# led_RGB_schematic.net
KiCad netlist of a schematic drawn in Altium Designer
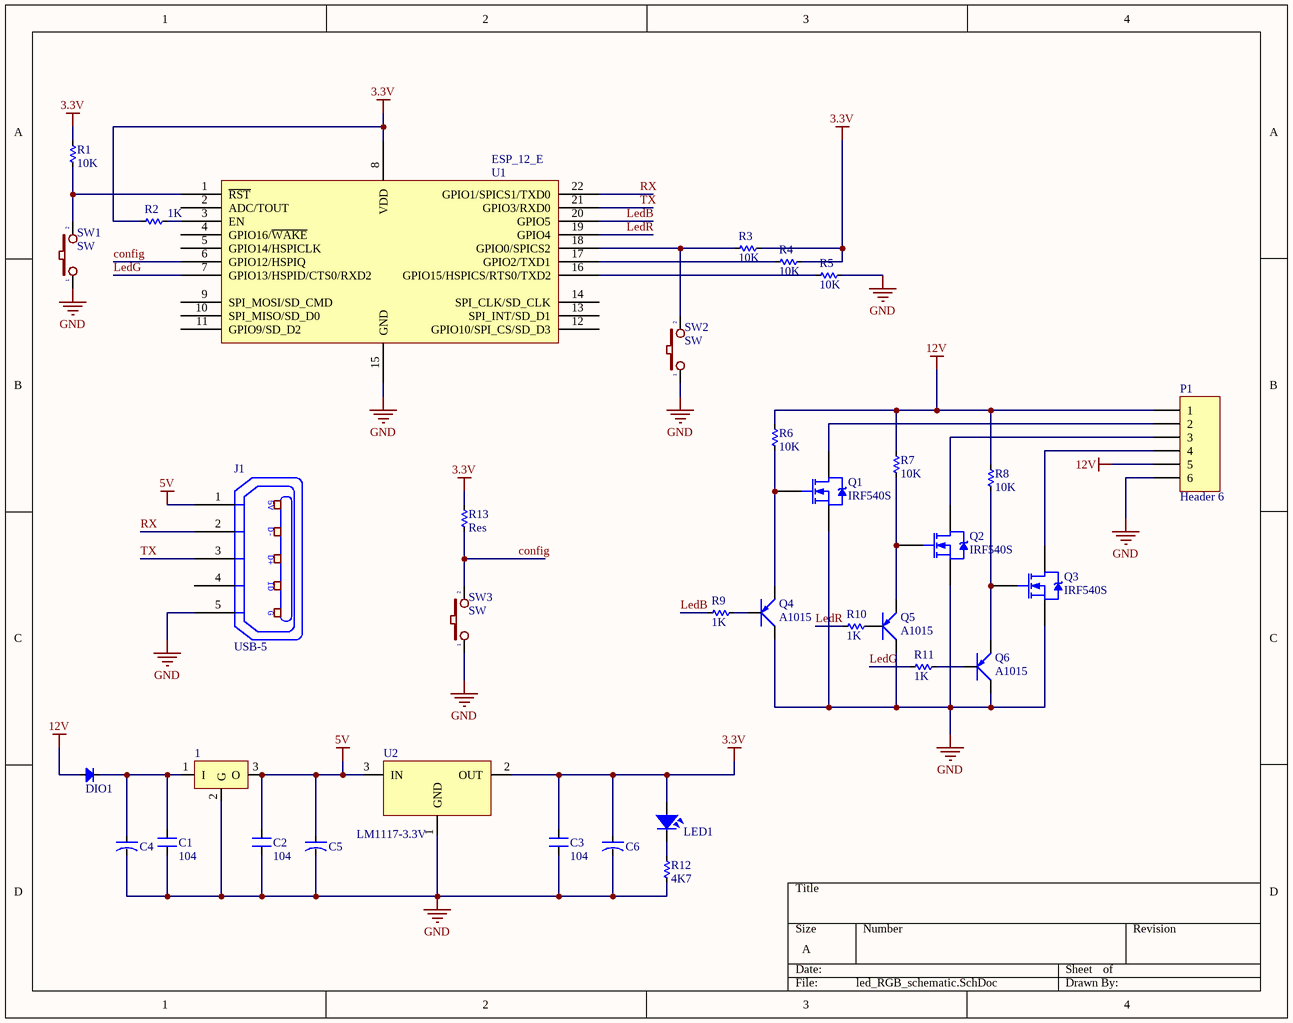
[diagram p0: led_RGB_schematic.SchDoc]

(export (version "E")
  (design (tool "Eeschema 10.0.6"))
  (components
    (comp (ref "1")
      (value "LM78xx")
      (footprint "TO252-123")
      (description "Positive Voltage Regulator")
      (fields (field (name "PUBLISHER") "Altium Limited"))
      (libsource (lib "LIBRARY") (part "LM78xx"))
    )
    (comp (ref "C1")
      (value "104")
      (footprint "SM-CAP-0805")
      (fields (field (name "DESIGNED BY") "VanDungEvn"))
      (libsource (lib "electronicvn-library1") (part "CN"))
    )
    (comp (ref "C2")
      (value "104")
      (footprint "SM-CAP-0805")
      (fields (field (name "DESIGNED BY") "VanDungEvn"))
      (libsource (lib "electronicvn-library1") (part "CN"))
    )
    (comp (ref "C3")
      (value "104")
      (footprint "SM-CAP-0805")
      (fields (field (name "DESIGNED BY") "VanDungEvn"))
      (libsource (lib "electronicvn-library1") (part "CN"))
    )
    (comp (ref "C4")
      (value "CN-ALU-SMD")
      (footprint "CAP-ALU-SMD-4.5x5x1.4")
      (description "Polarized Capacitor (Axial)")
      (fields (field (name "PUBLISHER") "Altium Limited"))
      (libsource (lib "LIBTanCN") (part "CN-ALU-SMD"))
    )
    (comp (ref "C5")
      (value "CN-ALU-SMD")
      (footprint "CAP-ALU-SMD-4.5x5x1.4")
      (description "Polarized Capacitor (Axial)")
      (fields (field (name "PUBLISHER") "Altium Limited"))
      (libsource (lib "LIBTanCN") (part "CN-ALU-SMD"))
    )
    (comp (ref "C6")
      (value "CN-ALU-SMD")
      (footprint "CAP-ALU-SMD-4.5x5x1.4")
      (description "Polarized Capacitor (Axial)")
      (fields (field (name "PUBLISHER") "Altium Limited"))
      (libsource (lib "LIBTanCN") (part "CN-ALU-SMD"))
    )
    (comp (ref "DIO1")
      (value "Diode SMD")
      (footprint "DIO-SMD-106")
      (description "Default Diode")
      (fields (field (name "PUBLISHER") "Altium Limited"))
      (libsource (lib "LIBRARY") (part "Diode SMD"))
    )
    (comp (ref "J1")
      (value "USB-5")
      (footprint "USB-M1")
      (fields
        (field (name "MANUFACTURER") "FCI")
        (field (name "MANUFACTURER PART NUMBER") "10118193-0001LF")
        (field (name ".CREATOR") "MM")
        (field (name ".CHECKED PCB") "RF")
        (field (name ".CHECKED SCH") "MM")
      )
      (libsource (lib "LIBRARY") (part "USB-5"))
    )
    (comp (ref "LED1") (value "LED") (footprint "LED-0805-Blue") (libsource (lib "LIBRARY") (part "LED SMD")))
    (comp (ref "P1")
      (value "Header 6")
      (footprint "HED6T")
      (description "Header, 6-Pin")
      (fields (field (name "PUBLISHER") "Altium Limited"))
      (libsource (lib "LIBTanCN") (part "Header 6"))
    )
    (comp (ref "Q1")
      (value "IRF540S")
      (footprint "D2PAK_N")
      (description "HEXFET N-Channel Power MOSFET")
      (fields (field (name "PUBLISHER") "Altium Limited"))
      (libsource (lib "IR Discrete MOSFET - Power") (part "IRF540S"))
    )
    (comp (ref "Q2")
      (value "IRF540S")
      (footprint "D2PAK_N")
      (description "HEXFET N-Channel Power MOSFET")
      (fields (field (name "PUBLISHER") "Altium Limited"))
      (libsource (lib "IR Discrete MOSFET - Power") (part "IRF540S"))
    )
    (comp (ref "Q3")
      (value "IRF540S")
      (footprint "D2PAK_N")
      (description "HEXFET N-Channel Power MOSFET")
      (fields (field (name "PUBLISHER") "Altium Limited"))
      (libsource (lib "IR Discrete MOSFET - Power") (part "IRF540S"))
    )
    (comp (ref "Q4")
      (value "A1015")
      (footprint "SOT23B")
      (description "PNP 600mW, ECB")
      (libsource (lib "electronicvn-library1") (part "A1015"))
    )
    (comp (ref "Q5")
      (value "A1015")
      (footprint "SOT23B")
      (description "PNP 600mW, ECB")
      (libsource (lib "electronicvn-library1") (part "A1015"))
    )
    (comp (ref "Q6")
      (value "A1015")
      (footprint "SOT23B")
      (description "PNP 600mW, ECB")
      (libsource (lib "electronicvn-library1") (part "A1015"))
    )
    (comp (ref "R1")
      (value "10K")
      (footprint "RES-SMD-0805")
      (description "Resistor")
      (fields
        (field (name "MANUFACTURER") "Generic Components")
        (field (name "PUBLISHER") "Altium Hobart Technology Centre")
      )
      (libsource (lib "LIBRARY") (part "Res-SMD"))
    )
    (comp (ref "R2")
      (value "1K")
      (footprint "RES-SMD-0805")
      (description "Resistor")
      (fields
        (field (name "MANUFACTURER") "Generic Components")
        (field (name "PUBLISHER") "Altium Hobart Technology Centre")
      )
      (libsource (lib "LIBRARY") (part "Res-SMD"))
    )
    (comp (ref "R3")
      (value "10K")
      (footprint "RES-SMD-0805")
      (description "Resistor")
      (fields
        (field (name "MANUFACTURER") "Generic Components")
        (field (name "PUBLISHER") "Altium Hobart Technology Centre")
      )
      (libsource (lib "LIBRARY") (part "Res-SMD"))
    )
    (comp (ref "R4")
      (value "10K")
      (footprint "RES-SMD-0805")
      (description "Resistor")
      (fields
        (field (name "MANUFACTURER") "Generic Components")
        (field (name "PUBLISHER") "Altium Hobart Technology Centre")
      )
      (libsource (lib "LIBRARY") (part "Res-SMD"))
    )
    (comp (ref "R5")
      (value "10K")
      (footprint "RES-SMD-0805")
      (description "Resistor")
      (fields
        (field (name "MANUFACTURER") "Generic Components")
        (field (name "PUBLISHER") "Altium Hobart Technology Centre")
      )
      (libsource (lib "LIBRARY") (part "Res-SMD"))
    )
    (comp (ref "R6")
      (value "10K")
      (footprint "RES-SMD-0805")
      (description "Resistor")
      (fields
        (field (name "MANUFACTURER") "Generic Components")
        (field (name "PUBLISHER") "Altium Hobart Technology Centre")
      )
      (libsource (lib "LIBRARY") (part "Res-SMD"))
    )
    (comp (ref "R7")
      (value "10K")
      (footprint "RES-SMD-0805")
      (description "Resistor")
      (fields
        (field (name "MANUFACTURER") "Generic Components")
        (field (name "PUBLISHER") "Altium Hobart Technology Centre")
      )
      (libsource (lib "LIBRARY") (part "Res-SMD"))
    )
    (comp (ref "R8")
      (value "10K")
      (footprint "RES-SMD-0805")
      (description "Resistor")
      (fields
        (field (name "MANUFACTURER") "Generic Components")
        (field (name "PUBLISHER") "Altium Hobart Technology Centre")
      )
      (libsource (lib "LIBRARY") (part "Res-SMD"))
    )
    (comp (ref "R9")
      (value "1K")
      (footprint "RES-SMD-0805")
      (description "Resistor")
      (fields
        (field (name "MANUFACTURER") "Generic Components")
        (field (name "PUBLISHER") "Altium Hobart Technology Centre")
      )
      (libsource (lib "LIBRARY") (part "Res-SMD"))
    )
    (comp (ref "R10")
      (value "1K")
      (footprint "RES-SMD-0805")
      (description "Resistor")
      (fields
        (field (name "MANUFACTURER") "Generic Components")
        (field (name "PUBLISHER") "Altium Hobart Technology Centre")
      )
      (libsource (lib "LIBRARY") (part "Res-SMD"))
    )
    (comp (ref "R11")
      (value "1K")
      (footprint "RES-SMD-0805")
      (description "Resistor")
      (fields
        (field (name "MANUFACTURER") "Generic Components")
        (field (name "PUBLISHER") "Altium Hobart Technology Centre")
      )
      (libsource (lib "LIBRARY") (part "Res-SMD"))
    )
    (comp (ref "R12")
      (value "4K7")
      (footprint "RES-SMD-0805")
      (description "Resistor")
      (fields
        (field (name "MANUFACTURER") "Generic Components")
        (field (name "PUBLISHER") "Altium Hobart Technology Centre")
      )
      (libsource (lib "LIBRARY") (part "Res-SMD"))
    )
    (comp (ref "R13")
      (value "Res")
      (footprint "RES-SMD-0805")
      (description "Resistor")
      (fields
        (field (name "MANUFACTURER") "Generic Components")
        (field (name "PUBLISHER") "Altium Hobart Technology Centre")
      )
      (libsource (lib "LIBRARY") (part "Res-SMD"))
    )
    (comp (ref "SW1")
      (value "SW")
      (footprint "SW1-SMD")
      (description "Switch button 2 pin")
      (libsource (lib "LIBRARY") (part "SW2"))
    )
    (comp (ref "SW2")
      (value "SW")
      (footprint "SW-DIP1-1")
      (description "Switch button 2 pin")
      (libsource (lib "LIBRARY") (part "SW2"))
    )
    (comp (ref "SW3")
      (value "SW")
      (footprint "SW2-D2")
      (description "Switch button 2 pin")
      (libsource (lib "LIBTanCN") (part "SW2"))
    )
    (comp (ref "U1")
      (value "ESP_12_E")
      (footprint "ESP_12_E")
      (description "ESP-12 Wi-Fi Module by AI-Thinker")
      (libsource (lib "ESP8266") (part "ESP_12_E"))
    )
    (comp (ref "U2")
      (value "LM1117-3.3V")
      (footprint "SOT223")
      (description "800mA Low-Dropout Linear Regulator")
      (fields (field (name "CREATOR") "Nguyen Ba Bien"))
      (libsource (lib "LIBRARY") (part "LM1117"))
    )
  )
  (nets
    (net (code "1") (name "/LedB") (class "Default")
      (node (ref "R9") (pin "1") (pinfunction "1_1") (pintype "passive"))
      (node (ref "U1") (pin "20") (pinfunction "GPIO5_20") (pintype "passive"))
    )
    (net (code "2") (name "/LedG") (class "Default")
      (node (ref "R11") (pin "1") (pinfunction "1_1") (pintype "passive"))
      (node (ref "U1") (pin "7") (pinfunction "GPIO13/HSPID/CTS0/RXD2_7") (pintype "passive"))
    )
    (net (code "3") (name "/LedR") (class "Default")
      (node (ref "R10") (pin "1") (pinfunction "1_1") (pintype "passive"))
      (node (ref "U1") (pin "19") (pinfunction "GPIO4_19") (pintype "passive"))
    )
    (net (code "4") (name "/RX") (class "Default")
      (node (ref "J1") (pin "2") (pinfunction "P2_2") (pintype "passive"))
      (node (ref "U1") (pin "22") (pinfunction "GPIO1/SPICS1/TXD0_22") (pintype "passive"))
    )
    (net (code "5") (name "/TX") (class "Default")
      (node (ref "J1") (pin "3") (pinfunction "P3_3") (pintype "passive"))
      (node (ref "U1") (pin "21") (pinfunction "GPIO3/RXD0_21") (pintype "passive"))
    )
    (net (code "6") (name "/config") (class "Default")
      (node (ref "R13") (pin "2") (pinfunction "2_2") (pintype "passive"))
      (node (ref "SW3") (pin "2") (pinfunction "2_2") (pintype "passive"))
      (node (ref "U1") (pin "6") (pinfunction "GPIO12/HSPIQ_6") (pintype "passive"))
    )
    (net (code "7") (name "3.3V") (class "Default")
      (node (ref "C3") (pin "2") (pinfunction "2_2") (pintype "passive"))
      (node (ref "C6") (pin "1") (pinfunction "1_1") (pintype "passive"))
      (node (ref "LED1") (pin "1") (pinfunction "1_1") (pintype "passive"))
      (node (ref "R1") (pin "1") (pinfunction "1_1") (pintype "passive"))
      (node (ref "R13") (pin "1") (pinfunction "1_1") (pintype "passive"))
      (node (ref "R2") (pin "2") (pinfunction "2_2") (pintype "passive"))
      (node (ref "R3") (pin "1") (pinfunction "1_1") (pintype "passive"))
      (node (ref "R4") (pin "1") (pinfunction "1_1") (pintype "passive"))
      (node (ref "U1") (pin "8") (pinfunction "VDD_8") (pintype "passive"))
      (node (ref "U2") (pin "2") (pinfunction "OUT_2") (pintype "passive"))
    )
    (net (code "8") (name "5V") (class "Default")
      (node (ref "1") (pin "3") (pinfunction "O_3") (pintype "power_in"))
      (node (ref "C2") (pin "2") (pinfunction "2_2") (pintype "passive"))
      (node (ref "C5") (pin "1") (pinfunction "1_1") (pintype "passive"))
      (node (ref "J1") (pin "1") (pinfunction "P1_1") (pintype "passive"))
      (node (ref "U2") (pin "3") (pinfunction "IN_3") (pintype "passive"))
    )
    (net (code "9") (name "12V") (class "Default")
      (node (ref "DIO1") (pin "1") (pinfunction "A_1") (pintype "passive"))
      (node (ref "P1") (pin "1") (pinfunction "1_1") (pintype "passive"))
      (node (ref "P1") (pin "5") (pinfunction "5_5") (pintype "passive"))
      (node (ref "R6") (pin "1") (pinfunction "1_1") (pintype "passive"))
      (node (ref "R7") (pin "1") (pinfunction "1_1") (pintype "passive"))
      (node (ref "R8") (pin "1") (pinfunction "1_1") (pintype "passive"))
    )
    (net (code "10") (name "GND") (class "Default")
      (node (ref "1") (pin "2") (pinfunction "G_2") (pintype "power_in"))
      (node (ref "C1") (pin "1") (pinfunction "1_1") (pintype "passive"))
      (node (ref "C2") (pin "1") (pinfunction "1_1") (pintype "passive"))
      (node (ref "C3") (pin "1") (pinfunction "1_1") (pintype "passive"))
      (node (ref "C4") (pin "2") (pinfunction "2_2") (pintype "passive"))
      (node (ref "C5") (pin "2") (pinfunction "2_2") (pintype "passive"))
      (node (ref "C6") (pin "2") (pinfunction "2_2") (pintype "passive"))
      (node (ref "J1") (pin "5") (pinfunction "P5_5") (pintype "passive"))
      (node (ref "P1") (pin "6") (pinfunction "6_6") (pintype "passive"))
      (node (ref "Q1") (pin "3") (pinfunction "S_3") (pintype "passive"))
      (node (ref "Q2") (pin "3") (pinfunction "S_3") (pintype "passive"))
      (node (ref "Q3") (pin "3") (pinfunction "S_3") (pintype "passive"))
      (node (ref "Q4") (pin "2") (pinfunction "C_2") (pintype "passive"))
      (node (ref "Q5") (pin "2") (pinfunction "C_2") (pintype "passive"))
      (node (ref "Q6") (pin "2") (pinfunction "C_2") (pintype "passive"))
      (node (ref "R12") (pin "2") (pinfunction "2_2") (pintype "passive"))
      (node (ref "R5") (pin "1") (pinfunction "1_1") (pintype "passive"))
      (node (ref "SW1") (pin "1") (pinfunction "1_1") (pintype "passive"))
      (node (ref "SW2") (pin "1") (pinfunction "1_1") (pintype "passive"))
      (node (ref "SW3") (pin "1") (pinfunction "1_1") (pintype "passive"))
      (node (ref "U1") (pin "15") (pinfunction "GND_15") (pintype "passive"))
      (node (ref "U2") (pin "1") (pinfunction "GND_1") (pintype "passive"))
    )
    (net (code "11") (name "Net-(1-I)") (class "Default")
      (node (ref "1") (pin "1") (pinfunction "I_1") (pintype "power_in"))
      (node (ref "C1") (pin "2") (pinfunction "2_2") (pintype "passive"))
      (node (ref "C4") (pin "1") (pinfunction "1_1") (pintype "passive"))
      (node (ref "DIO1") (pin "2") (pinfunction "K_2") (pintype "passive"))
    )
    (net (code "12") (name "Net-(LED1-Pad2)") (class "Default")
      (node (ref "LED1") (pin "2") (pinfunction "2_2") (pintype "passive"))
      (node (ref "R12") (pin "1") (pinfunction "1_1") (pintype "passive"))
    )
    (net (code "13") (name "Net-(Q1-D)") (class "Default")
      (node (ref "P1") (pin "2") (pinfunction "2_2") (pintype "passive"))
      (node (ref "Q1") (pin "2") (pinfunction "D_2") (pintype "passive"))
    )
    (net (code "14") (name "Net-(Q1-G)") (class "Default")
      (node (ref "Q1") (pin "1") (pinfunction "G_1") (pintype "passive"))
      (node (ref "Q4") (pin "1") (pinfunction "E_1") (pintype "passive"))
      (node (ref "R6") (pin "2") (pinfunction "2_2") (pintype "passive"))
    )
    (net (code "15") (name "Net-(Q2-D)") (class "Default")
      (node (ref "P1") (pin "3") (pinfunction "3_3") (pintype "passive"))
      (node (ref "Q2") (pin "2") (pinfunction "D_2") (pintype "passive"))
    )
    (net (code "16") (name "Net-(Q2-G)") (class "Default")
      (node (ref "Q2") (pin "1") (pinfunction "G_1") (pintype "passive"))
      (node (ref "Q5") (pin "1") (pinfunction "E_1") (pintype "passive"))
      (node (ref "R7") (pin "2") (pinfunction "2_2") (pintype "passive"))
    )
    (net (code "17") (name "Net-(Q3-D)") (class "Default")
      (node (ref "P1") (pin "4") (pinfunction "4_4") (pintype "passive"))
      (node (ref "Q3") (pin "2") (pinfunction "D_2") (pintype "passive"))
    )
    (net (code "18") (name "Net-(Q3-G)") (class "Default")
      (node (ref "Q3") (pin "1") (pinfunction "G_1") (pintype "passive"))
      (node (ref "Q6") (pin "1") (pinfunction "E_1") (pintype "passive"))
      (node (ref "R8") (pin "2") (pinfunction "2_2") (pintype "passive"))
    )
    (net (code "19") (name "Net-(Q4-B)") (class "Default")
      (node (ref "Q4") (pin "3") (pinfunction "B_3") (pintype "passive"))
      (node (ref "R9") (pin "2") (pinfunction "2_2") (pintype "passive"))
    )
    (net (code "20") (name "Net-(Q5-B)") (class "Default")
      (node (ref "Q5") (pin "3") (pinfunction "B_3") (pintype "passive"))
      (node (ref "R10") (pin "2") (pinfunction "2_2") (pintype "passive"))
    )
    (net (code "21") (name "Net-(Q6-B)") (class "Default")
      (node (ref "Q6") (pin "3") (pinfunction "B_3") (pintype "passive"))
      (node (ref "R11") (pin "2") (pinfunction "2_2") (pintype "passive"))
    )
    (net (code "22") (name "Net-(U1-EN)") (class "Default")
      (node (ref "R2") (pin "1") (pinfunction "1_1") (pintype "passive"))
      (node (ref "U1") (pin "3") (pinfunction "EN_3") (pintype "passive"))
    )
    (net (code "23") (name "Net-(U1-GPIO0{slash}SPICS2)") (class "Default")
      (node (ref "R3") (pin "2") (pinfunction "2_2") (pintype "passive"))
      (node (ref "SW2") (pin "2") (pinfunction "2_2") (pintype "passive"))
      (node (ref "U1") (pin "18") (pinfunction "GPIO0/SPICS2_18") (pintype "passive"))
    )
    (net (code "24") (name "Net-(U1-GPIO2{slash}TXD1)") (class "Default")
      (node (ref "R4") (pin "2") (pinfunction "2_2") (pintype "passive"))
      (node (ref "U1") (pin "17") (pinfunction "GPIO2/TXD1_17") (pintype "passive"))
    )
    (net (code "25") (name "Net-(U1-GPIO15{slash}HSPICS{slash}RTS0{slash}TXD2)") (class "Default")
      (node (ref "R5") (pin "2") (pinfunction "2_2") (pintype "passive"))
      (node (ref "U1") (pin "16") (pinfunction "GPIO15/HSPICS/RTS0/TXD2_16") (pintype "passive"))
    )
    (net (code "26") (name "Net-(U1-~{RST})") (class "Default")
      (node (ref "R1") (pin "2") (pinfunction "2_2") (pintype "passive"))
      (node (ref "SW1") (pin "2") (pinfunction "2_2") (pintype "passive"))
      (node (ref "U1") (pin "1") (pinfunction "~{RST}_1") (pintype "passive"))
    )
    (net (code "27") (name "unconnected-(J1-P4-Pad4)") (class "Default")
      (node (ref "J1") (pin "4") (pinfunction "P4_4") (pintype "passive"))
    )
    (net (code "28") (name "unconnected-(U1-ADC{slash}TOUT-Pad2)") (class "Default")
      (node (ref "U1") (pin "2") (pinfunction "ADC/TOUT_2") (pintype "passive"))
    )
    (net (code "29") (name "unconnected-(U1-GPIO9{slash}SD_D2-Pad11)") (class "Default")
      (node (ref "U1") (pin "11") (pinfunction "GPIO9/SD_D2_11") (pintype "passive"))
    )
    (net (code "30") (name "unconnected-(U1-GPIO10{slash}SPI_CS{slash}SD_D3-Pad12)") (class "Default")
      (node (ref "U1") (pin "12") (pinfunction "GPIO10/SPI_CS/SD_D3_12") (pintype "passive"))
    )
    (net (code "31") (name "unconnected-(U1-GPIO14{slash}HSPICLK-Pad5)") (class "Default")
      (node (ref "U1") (pin "5") (pinfunction "GPIO14/HSPICLK_5") (pintype "passive"))
    )
    (net (code "32") (name "unconnected-(U1-GPIO16{slash}~{WAKE}-Pad4)") (class "Default")
      (node (ref "U1") (pin "4") (pinfunction "GPIO16/~{WAKE}_4") (pintype "passive"))
    )
    (net (code "33") (name "unconnected-(U1-SPI_CLK{slash}SD_CLK-Pad14)") (class "Default")
      (node (ref "U1") (pin "14") (pinfunction "SPI_CLK/SD_CLK_14") (pintype "passive"))
    )
    (net (code "34") (name "unconnected-(U1-SPI_INT{slash}SD_D1-Pad13)") (class "Default")
      (node (ref "U1") (pin "13") (pinfunction "SPI_INT/SD_D1_13") (pintype "passive"))
    )
    (net (code "35") (name "unconnected-(U1-SPI_MISO{slash}SD_D0-Pad10)") (class "Default")
      (node (ref "U1") (pin "10") (pinfunction "SPI_MISO/SD_D0_10") (pintype "passive"))
    )
    (net (code "36") (name "unconnected-(U1-SPI_MOSI{slash}SD_CMD-Pad9)") (class "Default")
      (node (ref "U1") (pin "9") (pinfunction "SPI_MOSI/SD_CMD_9") (pintype "passive"))
    )
  )
)
